# 04_-_IMAGE_SENSORS.net
KiCad netlist of a schematic drawn in Altium Designer
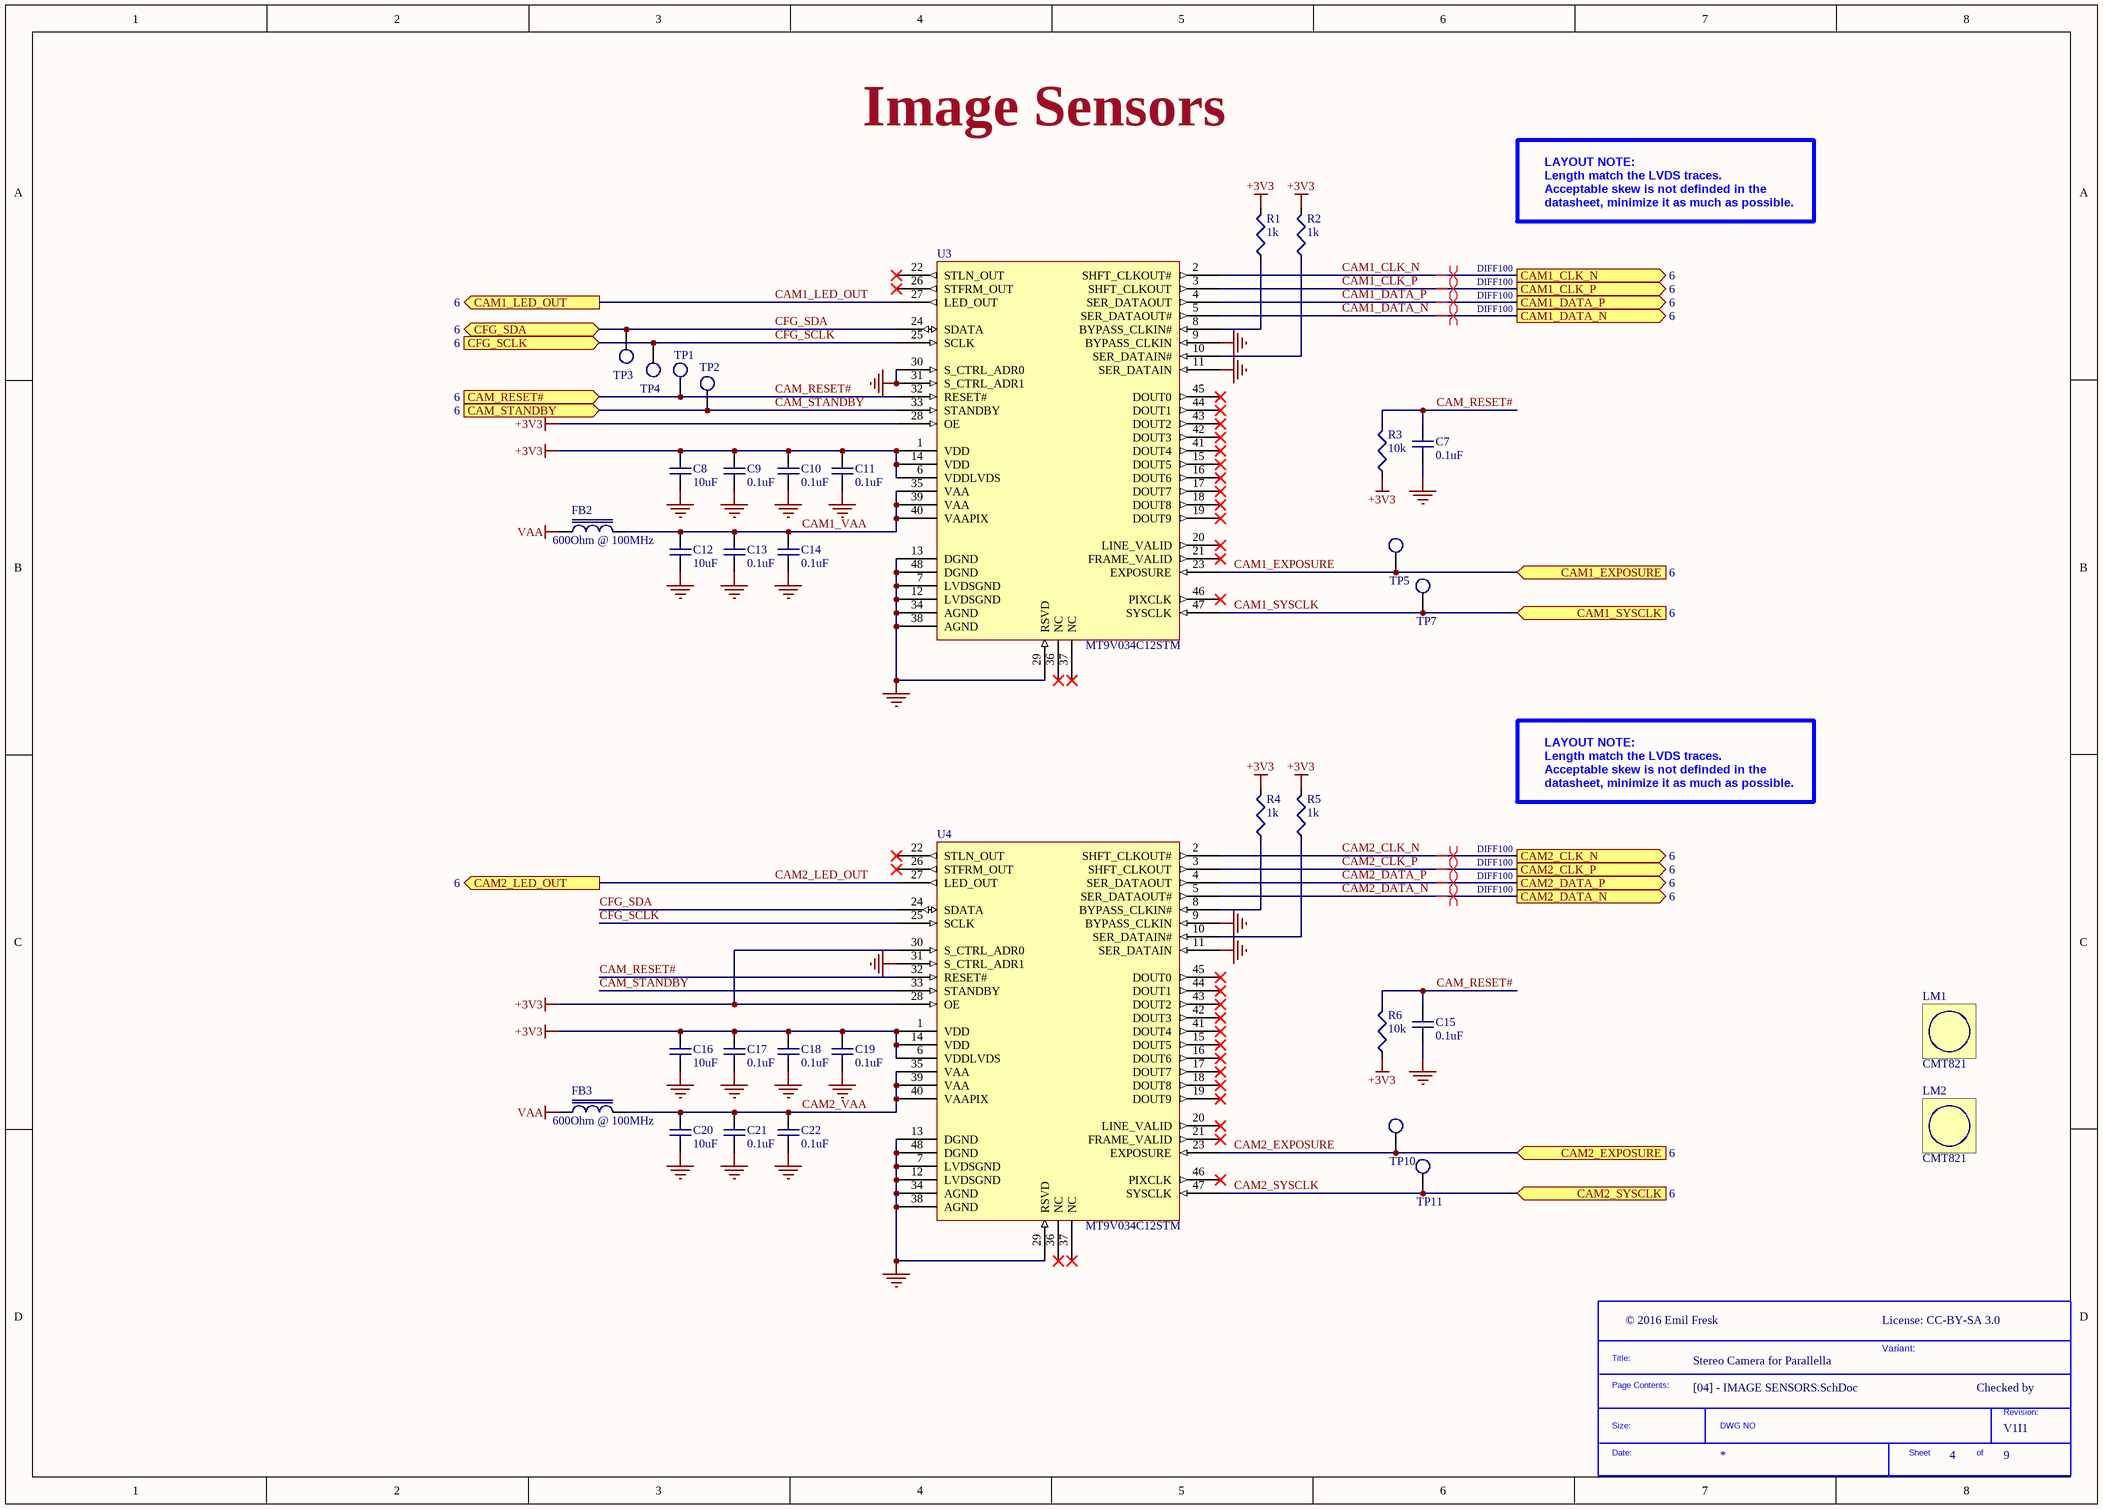
[diagram p0: [04] - IMAGE SENSORS.SchDoc]

(export (version "E")
  (design (tool "Eeschema 10.0.6"))
  (components
    (comp (ref "C7")
      (value "0.1uF")
      (footprint "C0603L")
      (description "CAP CER 0.1UF 50V 10% X7R 0603")
      (fields
        (field (name "MANUFACTURER") "Murata Electronics North America")
        (field (name "MANUFACTURER PART NUMBER") "GRM188R71H104KA93J")
      )
      (libsource (lib "Capacitors") (part "GRM188R71H104KA93J"))
    )
    (comp (ref "C8")
      (value "10uF")
      (footprint "C0603L")
      (description "CAP CER 10UF 16V 20% X5R 0603")
      (fields
        (field (name "MANUFACTURER") "Murata Electronics North America")
        (field (name "MANUFACTURER PART NUMBER") "GRM188R61C106MA73D")
      )
      (libsource (lib "Capacitors") (part "GRM188R61C106MA73D"))
    )
    (comp (ref "C9")
      (value "0.1uF")
      (footprint "C0603L")
      (description "CAP CER 0.1UF 50V 10% X7R 0603")
      (fields
        (field (name "MANUFACTURER") "Murata Electronics North America")
        (field (name "MANUFACTURER PART NUMBER") "GRM188R71H104KA93J")
      )
      (libsource (lib "Capacitors") (part "GRM188R71H104KA93J"))
    )
    (comp (ref "C10")
      (value "0.1uF")
      (footprint "C0603L")
      (description "CAP CER 0.1UF 50V 10% X7R 0603")
      (fields
        (field (name "MANUFACTURER") "Murata Electronics North America")
        (field (name "MANUFACTURER PART NUMBER") "GRM188R71H104KA93J")
      )
      (libsource (lib "Capacitors") (part "GRM188R71H104KA93J"))
    )
    (comp (ref "C11")
      (value "0.1uF")
      (footprint "C0603L")
      (description "CAP CER 0.1UF 50V 10% X7R 0603")
      (fields
        (field (name "MANUFACTURER") "Murata Electronics North America")
        (field (name "MANUFACTURER PART NUMBER") "GRM188R71H104KA93J")
      )
      (libsource (lib "Capacitors") (part "GRM188R71H104KA93J"))
    )
    (comp (ref "C12")
      (value "10uF")
      (footprint "C0603L")
      (description "CAP CER 10UF 16V 20% X5R 0603")
      (fields
        (field (name "MANUFACTURER") "Murata Electronics North America")
        (field (name "MANUFACTURER PART NUMBER") "GRM188R61C106MA73D")
      )
      (libsource (lib "Capacitors") (part "GRM188R61C106MA73D"))
    )
    (comp (ref "C13")
      (value "0.1uF")
      (footprint "C0603L")
      (description "CAP CER 0.1UF 50V 10% X7R 0603")
      (fields
        (field (name "MANUFACTURER") "Murata Electronics North America")
        (field (name "MANUFACTURER PART NUMBER") "GRM188R71H104KA93J")
      )
      (libsource (lib "Capacitors") (part "GRM188R71H104KA93J"))
    )
    (comp (ref "C14")
      (value "0.1uF")
      (footprint "C0603L")
      (description "CAP CER 0.1UF 50V 10% X7R 0603")
      (fields
        (field (name "MANUFACTURER") "Murata Electronics North America")
        (field (name "MANUFACTURER PART NUMBER") "GRM188R71H104KA93J")
      )
      (libsource (lib "Capacitors") (part "GRM188R71H104KA93J"))
    )
    (comp (ref "C15")
      (value "0.1uF")
      (footprint "C0603L")
      (description "CAP CER 0.1UF 50V 10% X7R 0603")
      (fields
        (field (name "MANUFACTURER") "Murata Electronics North America")
        (field (name "MANUFACTURER PART NUMBER") "GRM188R71H104KA93J")
      )
      (libsource (lib "Capacitors") (part "GRM188R71H104KA93J"))
    )
    (comp (ref "C16")
      (value "10uF")
      (footprint "C0603L")
      (description "CAP CER 10UF 16V 20% X5R 0603")
      (fields
        (field (name "MANUFACTURER") "Murata Electronics North America")
        (field (name "MANUFACTURER PART NUMBER") "GRM188R61C106MA73D")
      )
      (libsource (lib "Capacitors") (part "GRM188R61C106MA73D"))
    )
    (comp (ref "C17")
      (value "0.1uF")
      (footprint "C0603L")
      (description "CAP CER 0.1UF 50V 10% X7R 0603")
      (fields
        (field (name "MANUFACTURER") "Murata Electronics North America")
        (field (name "MANUFACTURER PART NUMBER") "GRM188R71H104KA93J")
      )
      (libsource (lib "Capacitors") (part "GRM188R71H104KA93J"))
    )
    (comp (ref "C18")
      (value "0.1uF")
      (footprint "C0603L")
      (description "CAP CER 0.1UF 50V 10% X7R 0603")
      (fields
        (field (name "MANUFACTURER") "Murata Electronics North America")
        (field (name "MANUFACTURER PART NUMBER") "GRM188R71H104KA93J")
      )
      (libsource (lib "Capacitors") (part "GRM188R71H104KA93J"))
    )
    (comp (ref "C19")
      (value "0.1uF")
      (footprint "C0603L")
      (description "CAP CER 0.1UF 50V 10% X7R 0603")
      (fields
        (field (name "MANUFACTURER") "Murata Electronics North America")
        (field (name "MANUFACTURER PART NUMBER") "GRM188R71H104KA93J")
      )
      (libsource (lib "Capacitors") (part "GRM188R71H104KA93J"))
    )
    (comp (ref "C20")
      (value "10uF")
      (footprint "C0603L")
      (description "CAP CER 10UF 16V 20% X5R 0603")
      (fields
        (field (name "MANUFACTURER") "Murata Electronics North America")
        (field (name "MANUFACTURER PART NUMBER") "GRM188R61C106MA73D")
      )
      (libsource (lib "Capacitors") (part "GRM188R61C106MA73D"))
    )
    (comp (ref "C21")
      (value "0.1uF")
      (footprint "C0603L")
      (description "CAP CER 0.1UF 50V 10% X7R 0603")
      (fields
        (field (name "MANUFACTURER") "Murata Electronics North America")
        (field (name "MANUFACTURER PART NUMBER") "GRM188R71H104KA93J")
      )
      (libsource (lib "Capacitors") (part "GRM188R71H104KA93J"))
    )
    (comp (ref "C22")
      (value "0.1uF")
      (footprint "C0603L")
      (description "CAP CER 0.1UF 50V 10% X7R 0603")
      (fields
        (field (name "MANUFACTURER") "Murata Electronics North America")
        (field (name "MANUFACTURER PART NUMBER") "GRM188R71H104KA93J")
      )
      (libsource (lib "Capacitors") (part "GRM188R71H104KA93J"))
    )
    (comp (ref "FB2")
      (value "600Ohm @ 100MHz")
      (footprint "R0603L")
      (description "FERRITE CHIP BEAD 600 OHM SMD")
      (fields
        (field (name "MANUFACTURER") "TDK Corporation")
        (field (name "MANUFACTURER PART NUMBER") "MPZ1608S601ATA00")
      )
      (libsource (lib "Inductors") (part "MPZ1608S601ATA00"))
    )
    (comp (ref "FB3")
      (value "600Ohm @ 100MHz")
      (footprint "R0603L")
      (description "FERRITE CHIP BEAD 600 OHM SMD")
      (fields
        (field (name "MANUFACTURER") "TDK Corporation")
        (field (name "MANUFACTURER PART NUMBER") "MPZ1608S601ATA00")
      )
      (libsource (lib "Inductors") (part "MPZ1608S601ATA00"))
    )
    (comp (ref "LM1")
      (value "CMT821")
      (footprint "CMT821 LENS HOLDER")
      (libsource (lib "Mechanical") (part "CMT821 LENS MOUNT"))
    )
    (comp (ref "LM2")
      (value "CMT821")
      (footprint "CMT821 LENS HOLDER")
      (libsource (lib "Mechanical") (part "CMT821 LENS MOUNT"))
    )
    (comp (ref "R1")
      (value "1k")
      (footprint "R0603L")
      (description "RES SMD 1K OHM 1% 1/10W 0603")
      (fields
        (field (name "MANUFACTURER") "Vishay Dale")
        (field (name "MANUFACTURER PART NUMBER") "CRCW06031K00FKEA")
      )
      (libsource (lib "Resistors") (part "CRCW06031K00FKEA"))
    )
    (comp (ref "R2")
      (value "1k")
      (footprint "R0603L")
      (description "RES SMD 1K OHM 1% 1/10W 0603")
      (fields
        (field (name "MANUFACTURER") "Vishay Dale")
        (field (name "MANUFACTURER PART NUMBER") "CRCW06031K00FKEA")
      )
      (libsource (lib "Resistors") (part "CRCW06031K00FKEA"))
    )
    (comp (ref "R3")
      (value "10k")
      (footprint "R0603L")
      (description "RES SMD 10K OHM 1% 1/10W 0603")
      (fields
        (field (name "MANUFACTURER") "Vishay Dale")
        (field (name "MANUFACTURER PART NUMBER") "CRCW060310K0FKEA")
      )
      (libsource (lib "Resistors") (part "CRCW060310K0FKEA"))
    )
    (comp (ref "R4")
      (value "1k")
      (footprint "R0603L")
      (description "RES SMD 1K OHM 1% 1/10W 0603")
      (fields
        (field (name "MANUFACTURER") "Vishay Dale")
        (field (name "MANUFACTURER PART NUMBER") "CRCW06031K00FKEA")
      )
      (libsource (lib "Resistors") (part "CRCW06031K00FKEA"))
    )
    (comp (ref "R5")
      (value "1k")
      (footprint "R0603L")
      (description "RES SMD 1K OHM 1% 1/10W 0603")
      (fields
        (field (name "MANUFACTURER") "Vishay Dale")
        (field (name "MANUFACTURER PART NUMBER") "CRCW06031K00FKEA")
      )
      (libsource (lib "Resistors") (part "CRCW06031K00FKEA"))
    )
    (comp (ref "R6")
      (value "10k")
      (footprint "R0603L")
      (description "RES SMD 10K OHM 1% 1/10W 0603")
      (fields
        (field (name "MANUFACTURER") "Vishay Dale")
        (field (name "MANUFACTURER PART NUMBER") "CRCW060310K0FKEA")
      )
      (libsource (lib "Resistors") (part "CRCW060310K0FKEA"))
    )
    (comp (ref "TP1")
      (value "TestPoint")
      (footprint "TestPoint_1.5mm")
      (libsource (lib "TestPoint") (part "TestPoint"))
    )
    (comp (ref "TP2")
      (value "TestPoint")
      (footprint "TestPoint_1.5mm")
      (libsource (lib "TestPoint") (part "TestPoint"))
    )
    (comp (ref "TP3")
      (value "TestPoint")
      (footprint "TestPoint_1.5mm")
      (libsource (lib "TestPoint") (part "TestPoint"))
    )
    (comp (ref "TP4")
      (value "TestPoint")
      (footprint "TestPoint_1.5mm")
      (libsource (lib "TestPoint") (part "TestPoint"))
    )
    (comp (ref "TP5")
      (value "TestPoint")
      (footprint "TestPoint_1.5mm")
      (libsource (lib "TestPoint") (part "TestPoint"))
    )
    (comp (ref "TP7")
      (value "TestPoint")
      (footprint "TestPoint_1.5mm")
      (libsource (lib "TestPoint") (part "TestPoint"))
    )
    (comp (ref "TP10")
      (value "TestPoint")
      (footprint "TestPoint_1.5mm")
      (libsource (lib "TestPoint") (part "TestPoint"))
    )
    (comp (ref "TP11")
      (value "TestPoint")
      (footprint "TestPoint_1.5mm")
      (libsource (lib "TestPoint") (part "TestPoint"))
    )
    (comp (ref "U3")
      (value "MT9V034C12STM")
      (footprint "LCC-48N_MT9V03X")
      (description "SENSOR IMAGE VGA MONO 48-CLCC")
      (fields (field (name "MANUFACTURER") "Aptina LLC"))
      (libsource (lib "Aptina") (part "MT9V034C12STM"))
    )
    (comp (ref "U4")
      (value "MT9V034C12STM")
      (footprint "LCC-48N_MT9V03X")
      (description "SENSOR IMAGE VGA MONO 48-CLCC")
      (fields (field (name "MANUFACTURER") "Aptina LLC"))
      (libsource (lib "Aptina") (part "MT9V034C12STM"))
    )
  )
  (nets
    (net (code "1") (name "+3V3") (class "Default")
      (node (ref "C10") (pin "1") (pinfunction "1_1") (pintype "passive"))
      (node (ref "C11") (pin "1") (pinfunction "1_1") (pintype "passive"))
      (node (ref "C16") (pin "1") (pinfunction "1_1") (pintype "passive"))
      (node (ref "C17") (pin "1") (pinfunction "1_1") (pintype "passive"))
      (node (ref "C18") (pin "1") (pinfunction "1_1") (pintype "passive"))
      (node (ref "C19") (pin "1") (pinfunction "1_1") (pintype "passive"))
      (node (ref "C8") (pin "1") (pinfunction "1_1") (pintype "passive"))
      (node (ref "C9") (pin "1") (pinfunction "1_1") (pintype "passive"))
      (node (ref "R1") (pin "2") (pinfunction "2_2") (pintype "passive"))
      (node (ref "R2") (pin "2") (pinfunction "2_2") (pintype "passive"))
      (node (ref "R3") (pin "1") (pinfunction "1_1") (pintype "passive"))
      (node (ref "R4") (pin "2") (pinfunction "2_2") (pintype "passive"))
      (node (ref "R5") (pin "2") (pinfunction "2_2") (pintype "passive"))
      (node (ref "R6") (pin "1") (pinfunction "1_1") (pintype "passive"))
      (node (ref "U3") (pin "1") (pinfunction "VDD_1") (pintype "power_in"))
      (node (ref "U3") (pin "14") (pinfunction "VDD_14") (pintype "power_in"))
      (node (ref "U3") (pin "28") (pinfunction "OE_28") (pintype "input"))
      (node (ref "U3") (pin "6") (pinfunction "VDDLVDS_6") (pintype "power_in"))
      (node (ref "U4") (pin "1") (pinfunction "VDD_1") (pintype "power_in"))
      (node (ref "U4") (pin "14") (pinfunction "VDD_14") (pintype "power_in"))
      (node (ref "U4") (pin "28") (pinfunction "OE_28") (pintype "input"))
      (node (ref "U4") (pin "30") (pinfunction "S_CTRL_ADR0_30") (pintype "input"))
      (node (ref "U4") (pin "6") (pinfunction "VDDLVDS_6") (pintype "power_in"))
    )
    (net (code "2") (name "/CAM1_CLK_N") (class "Default")
      (node (ref "U3") (pin "2") (pinfunction "SHFT_CLKOUT#_2") (pintype "output"))
    )
    (net (code "3") (name "/CAM1_CLK_P") (class "Default")
      (node (ref "U3") (pin "3") (pinfunction "SHFT_CLKOUT_3") (pintype "output"))
    )
    (net (code "4") (name "/CAM1_DATA_N") (class "Default")
      (node (ref "U3") (pin "5") (pinfunction "SER_DATAOUT#_5") (pintype "output"))
    )
    (net (code "5") (name "/CAM1_DATA_P") (class "Default")
      (node (ref "U3") (pin "4") (pinfunction "SER_DATAOUT_4") (pintype "output"))
    )
    (net (code "6") (name "/CAM1_EXPOSURE") (class "Default")
      (node (ref "TP5") (pin "1") (pinfunction "1_1") (pintype "passive"))
      (node (ref "U3") (pin "23") (pinfunction "EXPOSURE_23") (pintype "input"))
    )
    (net (code "7") (name "/CAM1_LED_OUT") (class "Default")
      (node (ref "U3") (pin "27") (pinfunction "LED_OUT_27") (pintype "output"))
    )
    (net (code "8") (name "/CAM1_SYSCLK") (class "Default")
      (node (ref "TP7") (pin "1") (pinfunction "1_1") (pintype "passive"))
      (node (ref "U3") (pin "47") (pinfunction "SYSCLK_47") (pintype "input"))
    )
    (net (code "9") (name "/CAM1_VAA") (class "Default")
      (node (ref "C12") (pin "1") (pinfunction "1_1") (pintype "passive"))
      (node (ref "C13") (pin "1") (pinfunction "1_1") (pintype "passive"))
      (node (ref "C14") (pin "1") (pinfunction "1_1") (pintype "passive"))
      (node (ref "FB2") (pin "2") (pinfunction "2_2") (pintype "passive"))
      (node (ref "U3") (pin "35") (pinfunction "VAA_35") (pintype "power_in"))
      (node (ref "U3") (pin "39") (pinfunction "VAA_39") (pintype "power_in"))
      (node (ref "U3") (pin "40") (pinfunction "VAAPIX_40") (pintype "power_in"))
    )
    (net (code "10") (name "/CAM2_CLK_N") (class "Default")
      (node (ref "U4") (pin "2") (pinfunction "SHFT_CLKOUT#_2") (pintype "output"))
    )
    (net (code "11") (name "/CAM2_CLK_P") (class "Default")
      (node (ref "U4") (pin "3") (pinfunction "SHFT_CLKOUT_3") (pintype "output"))
    )
    (net (code "12") (name "/CAM2_DATA_N") (class "Default")
      (node (ref "U4") (pin "5") (pinfunction "SER_DATAOUT#_5") (pintype "output"))
    )
    (net (code "13") (name "/CAM2_DATA_P") (class "Default")
      (node (ref "U4") (pin "4") (pinfunction "SER_DATAOUT_4") (pintype "output"))
    )
    (net (code "14") (name "/CAM2_EXPOSURE") (class "Default")
      (node (ref "TP10") (pin "1") (pinfunction "1_1") (pintype "passive"))
      (node (ref "U4") (pin "23") (pinfunction "EXPOSURE_23") (pintype "input"))
    )
    (net (code "15") (name "/CAM2_LED_OUT") (class "Default")
      (node (ref "U4") (pin "27") (pinfunction "LED_OUT_27") (pintype "output"))
    )
    (net (code "16") (name "/CAM2_SYSCLK") (class "Default")
      (node (ref "TP11") (pin "1") (pinfunction "1_1") (pintype "passive"))
      (node (ref "U4") (pin "47") (pinfunction "SYSCLK_47") (pintype "input"))
    )
    (net (code "17") (name "/CAM2_VAA") (class "Default")
      (node (ref "C20") (pin "1") (pinfunction "1_1") (pintype "passive"))
      (node (ref "C21") (pin "1") (pinfunction "1_1") (pintype "passive"))
      (node (ref "C22") (pin "1") (pinfunction "1_1") (pintype "passive"))
      (node (ref "FB3") (pin "2") (pinfunction "2_2") (pintype "passive"))
      (node (ref "U4") (pin "35") (pinfunction "VAA_35") (pintype "power_in"))
      (node (ref "U4") (pin "39") (pinfunction "VAA_39") (pintype "power_in"))
      (node (ref "U4") (pin "40") (pinfunction "VAAPIX_40") (pintype "power_in"))
    )
    (net (code "18") (name "/CAM_RESET#") (class "Default")
      (node (ref "C15") (pin "1") (pinfunction "1_1") (pintype "passive"))
      (node (ref "C7") (pin "1") (pinfunction "1_1") (pintype "passive"))
      (node (ref "R3") (pin "2") (pinfunction "2_2") (pintype "passive"))
      (node (ref "R6") (pin "2") (pinfunction "2_2") (pintype "passive"))
      (node (ref "TP1") (pin "1") (pinfunction "1_1") (pintype "passive"))
      (node (ref "U3") (pin "32") (pinfunction "RESET#_32") (pintype "input"))
      (node (ref "U4") (pin "32") (pinfunction "RESET#_32") (pintype "input"))
    )
    (net (code "19") (name "/CAM_STANDBY") (class "Default")
      (node (ref "TP2") (pin "1") (pinfunction "1_1") (pintype "passive"))
      (node (ref "U3") (pin "33") (pinfunction "STANDBY_33") (pintype "input"))
      (node (ref "U4") (pin "33") (pinfunction "STANDBY_33") (pintype "input"))
    )
    (net (code "20") (name "/CFG_SCLK") (class "Default")
      (node (ref "TP4") (pin "1") (pinfunction "1_1") (pintype "passive"))
      (node (ref "U3") (pin "25") (pinfunction "SCLK_25") (pintype "input"))
      (node (ref "U4") (pin "25") (pinfunction "SCLK_25") (pintype "input"))
    )
    (net (code "21") (name "/CFG_SDA") (class "Default")
      (node (ref "TP3") (pin "1") (pinfunction "1_1") (pintype "passive"))
      (node (ref "U3") (pin "24") (pinfunction "SDATA_24") (pintype "bidirectional"))
      (node (ref "U4") (pin "24") (pinfunction "SDATA_24") (pintype "bidirectional"))
    )
    (net (code "22") (name "GND") (class "Default")
      (node (ref "C10") (pin "2") (pinfunction "2_2") (pintype "passive"))
      (node (ref "C11") (pin "2") (pinfunction "2_2") (pintype "passive"))
      (node (ref "C12") (pin "2") (pinfunction "2_2") (pintype "passive"))
      (node (ref "C13") (pin "2") (pinfunction "2_2") (pintype "passive"))
      (node (ref "C14") (pin "2") (pinfunction "2_2") (pintype "passive"))
      (node (ref "C15") (pin "2") (pinfunction "2_2") (pintype "passive"))
      (node (ref "C16") (pin "2") (pinfunction "2_2") (pintype "passive"))
      (node (ref "C17") (pin "2") (pinfunction "2_2") (pintype "passive"))
      (node (ref "C18") (pin "2") (pinfunction "2_2") (pintype "passive"))
      (node (ref "C19") (pin "2") (pinfunction "2_2") (pintype "passive"))
      (node (ref "C20") (pin "2") (pinfunction "2_2") (pintype "passive"))
      (node (ref "C21") (pin "2") (pinfunction "2_2") (pintype "passive"))
      (node (ref "C22") (pin "2") (pinfunction "2_2") (pintype "passive"))
      (node (ref "C7") (pin "2") (pinfunction "2_2") (pintype "passive"))
      (node (ref "C8") (pin "2") (pinfunction "2_2") (pintype "passive"))
      (node (ref "C9") (pin "2") (pinfunction "2_2") (pintype "passive"))
      (node (ref "U3") (pin "11") (pinfunction "SER_DATAIN_11") (pintype "input"))
      (node (ref "U3") (pin "12") (pinfunction "LVDSGND_12") (pintype "power_in"))
      (node (ref "U3") (pin "13") (pinfunction "DGND_13") (pintype "power_in"))
      (node (ref "U3") (pin "29") (pinfunction "RSVD_29") (pintype "input"))
      (node (ref "U3") (pin "30") (pinfunction "S_CTRL_ADR0_30") (pintype "input"))
      (node (ref "U3") (pin "31") (pinfunction "S_CTRL_ADR1_31") (pintype "input"))
      (node (ref "U3") (pin "34") (pinfunction "AGND_34") (pintype "power_in"))
      (node (ref "U3") (pin "38") (pinfunction "AGND_38") (pintype "power_in"))
      (node (ref "U3") (pin "48") (pinfunction "DGND_48") (pintype "power_in"))
      (node (ref "U3") (pin "7") (pinfunction "LVDSGND_7") (pintype "power_in"))
      (node (ref "U3") (pin "9") (pinfunction "BYPASS_CLKIN_9") (pintype "input"))
      (node (ref "U4") (pin "11") (pinfunction "SER_DATAIN_11") (pintype "input"))
      (node (ref "U4") (pin "12") (pinfunction "LVDSGND_12") (pintype "power_in"))
      (node (ref "U4") (pin "13") (pinfunction "DGND_13") (pintype "power_in"))
      (node (ref "U4") (pin "29") (pinfunction "RSVD_29") (pintype "input"))
      (node (ref "U4") (pin "31") (pinfunction "S_CTRL_ADR1_31") (pintype "input"))
      (node (ref "U4") (pin "34") (pinfunction "AGND_34") (pintype "power_in"))
      (node (ref "U4") (pin "38") (pinfunction "AGND_38") (pintype "power_in"))
      (node (ref "U4") (pin "48") (pinfunction "DGND_48") (pintype "power_in"))
      (node (ref "U4") (pin "7") (pinfunction "LVDSGND_7") (pintype "power_in"))
      (node (ref "U4") (pin "9") (pinfunction "BYPASS_CLKIN_9") (pintype "input"))
    )
    (net (code "23") (name "Net-(U3-BYPASS_CLKIN#)") (class "Default")
      (node (ref "R1") (pin "1") (pinfunction "1_1") (pintype "passive"))
      (node (ref "U3") (pin "8") (pinfunction "BYPASS_CLKIN#_8") (pintype "input"))
    )
    (net (code "24") (name "Net-(U3-SER_DATAIN#)") (class "Default")
      (node (ref "R2") (pin "1") (pinfunction "1_1") (pintype "passive"))
      (node (ref "U3") (pin "10") (pinfunction "SER_DATAIN#_10") (pintype "input"))
    )
    (net (code "25") (name "Net-(U4-BYPASS_CLKIN#)") (class "Default")
      (node (ref "R4") (pin "1") (pinfunction "1_1") (pintype "passive"))
      (node (ref "U4") (pin "8") (pinfunction "BYPASS_CLKIN#_8") (pintype "input"))
    )
    (net (code "26") (name "Net-(U4-SER_DATAIN#)") (class "Default")
      (node (ref "R5") (pin "1") (pinfunction "1_1") (pintype "passive"))
      (node (ref "U4") (pin "10") (pinfunction "SER_DATAIN#_10") (pintype "input"))
    )
    (net (code "27") (name "VAA") (class "Default")
      (node (ref "FB2") (pin "1") (pinfunction "1_1") (pintype "passive"))
      (node (ref "FB3") (pin "1") (pinfunction "1_1") (pintype "passive"))
    )
    (net (code "28") (name "unconnected-(U3-DOUT0-Pad45)") (class "Default")
      (node (ref "U3") (pin "45") (pinfunction "DOUT0_45") (pintype "output+no_connect"))
    )
    (net (code "29") (name "unconnected-(U3-DOUT1-Pad44)") (class "Default")
      (node (ref "U3") (pin "44") (pinfunction "DOUT1_44") (pintype "output+no_connect"))
    )
    (net (code "30") (name "unconnected-(U3-DOUT2-Pad43)") (class "Default")
      (node (ref "U3") (pin "43") (pinfunction "DOUT2_43") (pintype "output+no_connect"))
    )
    (net (code "31") (name "unconnected-(U3-DOUT3-Pad42)") (class "Default")
      (node (ref "U3") (pin "42") (pinfunction "DOUT3_42") (pintype "output+no_connect"))
    )
    (net (code "32") (name "unconnected-(U3-DOUT4-Pad41)") (class "Default")
      (node (ref "U3") (pin "41") (pinfunction "DOUT4_41") (pintype "output+no_connect"))
    )
    (net (code "33") (name "unconnected-(U3-DOUT5-Pad15)") (class "Default")
      (node (ref "U3") (pin "15") (pinfunction "DOUT5_15") (pintype "output+no_connect"))
    )
    (net (code "34") (name "unconnected-(U3-DOUT6-Pad16)") (class "Default")
      (node (ref "U3") (pin "16") (pinfunction "DOUT6_16") (pintype "output+no_connect"))
    )
    (net (code "35") (name "unconnected-(U3-DOUT7-Pad17)") (class "Default")
      (node (ref "U3") (pin "17") (pinfunction "DOUT7_17") (pintype "output+no_connect"))
    )
    (net (code "36") (name "unconnected-(U3-DOUT8-Pad18)") (class "Default")
      (node (ref "U3") (pin "18") (pinfunction "DOUT8_18") (pintype "output+no_connect"))
    )
    (net (code "37") (name "unconnected-(U3-DOUT9-Pad19)") (class "Default")
      (node (ref "U3") (pin "19") (pinfunction "DOUT9_19") (pintype "output+no_connect"))
    )
    (net (code "38") (name "unconnected-(U3-FRAME_VALID-Pad21)") (class "Default")
      (node (ref "U3") (pin "21") (pinfunction "FRAME_VALID_21") (pintype "output+no_connect"))
    )
    (net (code "39") (name "unconnected-(U3-LINE_VALID-Pad20)") (class "Default")
      (node (ref "U3") (pin "20") (pinfunction "LINE_VALID_20") (pintype "output+no_connect"))
    )
    (net (code "40") (name "unconnected-(U3-NC-Pad36)") (class "Default")
      (node (ref "U3") (pin "36") (pinfunction "NC_36") (pintype "passive+no_connect"))
    )
    (net (code "41") (name "unconnected-(U3-NC-Pad37)") (class "Default")
      (node (ref "U3") (pin "37") (pinfunction "NC_37") (pintype "passive+no_connect"))
    )
    (net (code "42") (name "unconnected-(U3-PIXCLK-Pad46)") (class "Default")
      (node (ref "U3") (pin "46") (pinfunction "PIXCLK_46") (pintype "output+no_connect"))
    )
    (net (code "43") (name "unconnected-(U3-STFRM_OUT-Pad26)") (class "Default")
      (node (ref "U3") (pin "26") (pinfunction "STFRM_OUT_26") (pintype "output+no_connect"))
    )
    (net (code "44") (name "unconnected-(U3-STLN_OUT-Pad22)") (class "Default")
      (node (ref "U3") (pin "22") (pinfunction "STLN_OUT_22") (pintype "output+no_connect"))
    )
    (net (code "45") (name "unconnected-(U4-DOUT0-Pad45)") (class "Default")
      (node (ref "U4") (pin "45") (pinfunction "DOUT0_45") (pintype "output+no_connect"))
    )
    (net (code "46") (name "unconnected-(U4-DOUT1-Pad44)") (class "Default")
      (node (ref "U4") (pin "44") (pinfunction "DOUT1_44") (pintype "output+no_connect"))
    )
    (net (code "47") (name "unconnected-(U4-DOUT2-Pad43)") (class "Default")
      (node (ref "U4") (pin "43") (pinfunction "DOUT2_43") (pintype "output+no_connect"))
    )
    (net (code "48") (name "unconnected-(U4-DOUT3-Pad42)") (class "Default")
      (node (ref "U4") (pin "42") (pinfunction "DOUT3_42") (pintype "output+no_connect"))
    )
    (net (code "49") (name "unconnected-(U4-DOUT4-Pad41)") (class "Default")
      (node (ref "U4") (pin "41") (pinfunction "DOUT4_41") (pintype "output+no_connect"))
    )
    (net (code "50") (name "unconnected-(U4-DOUT5-Pad15)") (class "Default")
      (node (ref "U4") (pin "15") (pinfunction "DOUT5_15") (pintype "output+no_connect"))
    )
    (net (code "51") (name "unconnected-(U4-DOUT6-Pad16)") (class "Default")
      (node (ref "U4") (pin "16") (pinfunction "DOUT6_16") (pintype "output+no_connect"))
    )
    (net (code "52") (name "unconnected-(U4-DOUT7-Pad17)") (class "Default")
      (node (ref "U4") (pin "17") (pinfunction "DOUT7_17") (pintype "output+no_connect"))
    )
    (net (code "53") (name "unconnected-(U4-DOUT8-Pad18)") (class "Default")
      (node (ref "U4") (pin "18") (pinfunction "DOUT8_18") (pintype "output+no_connect"))
    )
    (net (code "54") (name "unconnected-(U4-DOUT9-Pad19)") (class "Default")
      (node (ref "U4") (pin "19") (pinfunction "DOUT9_19") (pintype "output+no_connect"))
    )
    (net (code "55") (name "unconnected-(U4-FRAME_VALID-Pad21)") (class "Default")
      (node (ref "U4") (pin "21") (pinfunction "FRAME_VALID_21") (pintype "output+no_connect"))
    )
    (net (code "56") (name "unconnected-(U4-LINE_VALID-Pad20)") (class "Default")
      (node (ref "U4") (pin "20") (pinfunction "LINE_VALID_20") (pintype "output+no_connect"))
    )
    (net (code "57") (name "unconnected-(U4-NC-Pad36)") (class "Default")
      (node (ref "U4") (pin "36") (pinfunction "NC_36") (pintype "passive+no_connect"))
    )
    (net (code "58") (name "unconnected-(U4-NC-Pad37)") (class "Default")
      (node (ref "U4") (pin "37") (pinfunction "NC_37") (pintype "passive+no_connect"))
    )
    (net (code "59") (name "unconnected-(U4-PIXCLK-Pad46)") (class "Default")
      (node (ref "U4") (pin "46") (pinfunction "PIXCLK_46") (pintype "output+no_connect"))
    )
    (net (code "60") (name "unconnected-(U4-STFRM_OUT-Pad26)") (class "Default")
      (node (ref "U4") (pin "26") (pinfunction "STFRM_OUT_26") (pintype "output+no_connect"))
    )
    (net (code "61") (name "unconnected-(U4-STLN_OUT-Pad22)") (class "Default")
      (node (ref "U4") (pin "22") (pinfunction "STLN_OUT_22") (pintype "output+no_connect"))
    )
  )
)
